# LM3404prototype.net
KiCad netlist of a schematic drawn in EAGLE
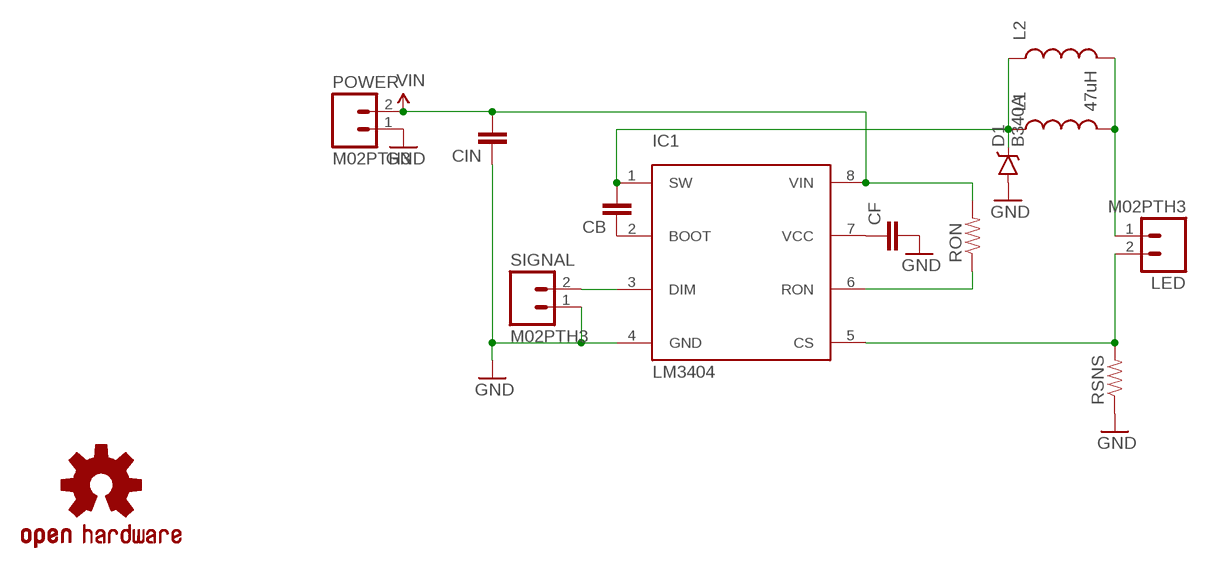
[diagram p0: schematic, sheet 1]

(export (version "E")
  (design (tool "Eeschema 10.0.6"))
  (components
    (comp (ref "CB")
      (value "CAP1206")
      (footprint "eagle-import:1206")
      (libsource (lib "eagle-import") (part "CAP1206"))
    )
    (comp (ref "CF")
      (value "CAP1206")
      (footprint "eagle-import:1206")
      (libsource (lib "eagle-import") (part "CAP1206"))
    )
    (comp (ref "CIN")
      (value "CAP1206")
      (footprint "eagle-import:1206")
      (libsource (lib "eagle-import") (part "CAP1206"))
    )
    (comp (ref "D1")
      (value "B340A")
      (footprint "eagle-import:SMA-DIODE")
      (libsource (lib "eagle-import") (part "DIODE-SCHOTTKY-B340A"))
    )
    (comp (ref "IC1")
      (value "LM3404")
      (footprint "eagle-import:SO8")
      (libsource (lib "eagle-import") (part "LM3404"))
    )
    (comp (ref "L1")
      (value "47uH")
      (footprint "eagle-import:CR75")
      (libsource (lib "eagle-import") (part "SparkFun-Passives_INDUCTOR68UH-1A"))
    )
    (comp (ref "L2")
      (value "INDUCTORSDR1105")
      (footprint "eagle-import:B82462G")
      (libsource (lib "eagle-import") (part "INDUCTORSDR1105"))
    )
    (comp (ref "LED")
      (value "M02PTH3")
      (footprint "eagle-import:1X02_LONGPADS")
      (libsource (lib "eagle-import") (part "M02PTH3"))
    )
    (comp (ref "LOGO1")
      (value "OSHW-LOGOS")
      (footprint "eagle-import:OSHW-LOGO-S")
      (libsource (lib "eagle-import") (part "OSHW-LOGOS"))
    )
    (comp (ref "POWER")
      (value "M02PTH3")
      (footprint "eagle-import:1X02_LONGPADS")
      (libsource (lib "eagle-import") (part "M02PTH3"))
    )
    (comp (ref "RON")
      (value "RESISTOR1206")
      (footprint "eagle-import:1206")
      (libsource (lib "eagle-import") (part "RESISTOR1206"))
    )
    (comp (ref "RSNS")
      (value "RESISTOR1206")
      (footprint "eagle-import:1206")
      (libsource (lib "eagle-import") (part "RESISTOR1206"))
    )
    (comp (ref "SIGNAL")
      (value "M02PTH3")
      (footprint "eagle-import:1X02_LONGPADS")
      (libsource (lib "eagle-import") (part "M02PTH3"))
    )
  )
  (nets
    (net (code "1") (name "GND") (class "Default")
      (node (ref "CF") (pin "2") (pinfunction "2_2") (pintype "passive"))
      (node (ref "CIN") (pin "1") (pinfunction "1_1") (pintype "passive"))
      (node (ref "D1") (pin "A") (pinfunction "A_A") (pintype "passive"))
      (node (ref "IC1") (pin "4") (pinfunction "GND_4") (pintype "bidirectional"))
      (node (ref "POWER") (pin "1") (pinfunction "1_1") (pintype "passive"))
      (node (ref "RSNS") (pin "1") (pinfunction "1_1") (pintype "passive"))
      (node (ref "SIGNAL") (pin "1") (pinfunction "1_1") (pintype "passive"))
    )
    (net (code "2") (name "Net-(IC1-BOOT)") (class "Default")
      (node (ref "CB") (pin "1") (pinfunction "1_1") (pintype "passive"))
      (node (ref "IC1") (pin "2") (pinfunction "BOOT_2") (pintype "bidirectional"))
    )
    (net (code "3") (name "Net-(IC1-CS)") (class "Default")
      (node (ref "IC1") (pin "5") (pinfunction "CS_5") (pintype "bidirectional"))
      (node (ref "LED") (pin "2") (pinfunction "2_2") (pintype "passive"))
      (node (ref "RSNS") (pin "2") (pinfunction "2_2") (pintype "passive"))
    )
    (net (code "4") (name "Net-(IC1-DIM)") (class "Default")
      (node (ref "IC1") (pin "3") (pinfunction "DIM_3") (pintype "bidirectional"))
      (node (ref "SIGNAL") (pin "2") (pinfunction "2_2") (pintype "passive"))
    )
    (net (code "5") (name "Net-(IC1-RON)") (class "Default")
      (node (ref "IC1") (pin "6") (pinfunction "RON_6") (pintype "bidirectional"))
      (node (ref "RON") (pin "1") (pinfunction "1_1") (pintype "passive"))
    )
    (net (code "6") (name "Net-(IC1-SW)") (class "Default")
      (node (ref "CB") (pin "2") (pinfunction "2_2") (pintype "passive"))
      (node (ref "D1") (pin "C") (pinfunction "C_C") (pintype "passive"))
      (node (ref "IC1") (pin "1") (pinfunction "SW_1") (pintype "bidirectional"))
      (node (ref "L1") (pin "P$1") (pinfunction "1_P$1") (pintype "passive"))
      (node (ref "L2") (pin "P$1") (pinfunction "1_P$1") (pintype "passive"))
    )
    (net (code "7") (name "Net-(IC1-VCC)") (class "Default")
      (node (ref "CF") (pin "1") (pinfunction "1_1") (pintype "passive"))
      (node (ref "IC1") (pin "7") (pinfunction "VCC_7") (pintype "bidirectional"))
    )
    (net (code "8") (name "Net-(L1-2)") (class "Default")
      (node (ref "L1") (pin "P$2") (pinfunction "2_P$2") (pintype "passive"))
      (node (ref "L2") (pin "P$2") (pinfunction "2_P$2") (pintype "passive"))
      (node (ref "LED") (pin "1") (pinfunction "1_1") (pintype "passive"))
    )
    (net (code "9") (name "VIN") (class "Default")
      (node (ref "CIN") (pin "2") (pinfunction "2_2") (pintype "passive"))
      (node (ref "IC1") (pin "8") (pinfunction "VIN_8") (pintype "bidirectional"))
      (node (ref "POWER") (pin "2") (pinfunction "2_2") (pintype "passive"))
      (node (ref "RON") (pin "2") (pinfunction "2_2") (pintype "passive"))
    )
  )
)
